# Blink_Blink_Beep_Boop.net
KiCad netlist of a schematic drawn in Altium Designer
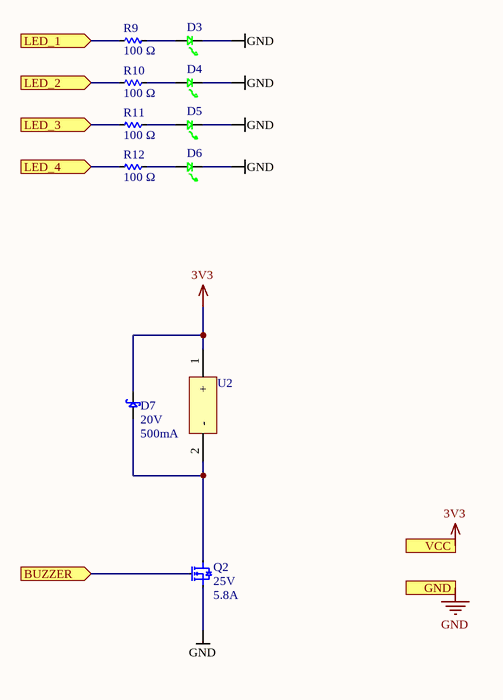
[diagram p0: Blink_Blink_Beep_Boop.SchDoc]

(export (version "E")
  (design (tool "Eeschema 10.0.6"))
  (components
    (comp (ref "D3")
      (value "LED_LY971")
      (footprint "0805_Diode")
      (description "LED 0805 GREEN 20MA")
      (fields
        (field (name "MANUFACTURER") "OSRAM Opto Semiconductors Inc")
        (field (name "MANUFACTURER PART NUMBER") "LG R971-KN-1")
      )
      (libsource (lib "Stanford Student Space Initiative") (part "LED_LY971"))
    )
    (comp (ref "D4")
      (value "LED_LY971")
      (footprint "0805_Diode")
      (description "LED 0805 GREEN 20MA")
      (fields
        (field (name "MANUFACTURER") "OSRAM Opto Semiconductors Inc")
        (field (name "MANUFACTURER PART NUMBER") "LG R971-KN-1")
      )
      (libsource (lib "Stanford Student Space Initiative") (part "LED_LY971"))
    )
    (comp (ref "D5")
      (value "LED_LY971")
      (footprint "0805_Diode")
      (description "LED 0805 GREEN 20MA")
      (fields
        (field (name "MANUFACTURER") "OSRAM Opto Semiconductors Inc")
        (field (name "MANUFACTURER PART NUMBER") "LG R971-KN-1")
      )
      (libsource (lib "Stanford Student Space Initiative") (part "LED_LY971"))
    )
    (comp (ref "D6")
      (value "LED_LY971")
      (footprint "0805_Diode")
      (description "LED 0805 GREEN 20MA")
      (fields
        (field (name "MANUFACTURER") "OSRAM Opto Semiconductors Inc")
        (field (name "MANUFACTURER PART NUMBER") "LG R971-KN-1")
      )
      (libsource (lib "Stanford Student Space Initiative") (part "LED_LY971"))
    )
    (comp (ref "D7")
      (value "Symbol")
      (footprint "SOD123")
      (description "DIODE SCHOTTKY 0.5A 20V SOD-123")
      (fields
        (field (name "MANUFACTURER") "Fairchild Semiconductor")
        (field (name "MANUFACTURER PART NUMBER") "MBR0520L")
        (field (name "VOLTAGE - DC REVERSE (VR) (MAX)") "20V")
        (field (name "CURRENT - AVERAGE RECTIFIED (IO)") "500mA")
      )
      (libsource (lib "Stanford Student Space Initiative") (part "Symbol"))
    )
    (comp (ref "Q2")
      (value "Symbol")
      (footprint "3SOT23")
      (description "MOSFET N-CH 25V 5.8A SOT23")
      (fields
        (field (name "MANUFACTURER") "International Rectifier")
        (field (name "MANUFACTURER PART NUMBER") "IRFML8244TRPBF")
        (field (name "DRAIN TO SOURCE VOLTAGE (VDSS)") "25V")
        (field (name "CURRENT - CONTINUOUS DRAIN (ID) @ 25° C") "5.8A")
      )
      (libsource (lib "") (part "Symbol_1"))
    )
    (comp (ref "R9")
      (value "311-100HRCT-ND")
      (footprint "R0603")
      (description "RES SMD 100 OHM 1% 1/10W 0603")
      (fields
        (field (name "MANUFACTURER PART NUMBER") "RC0603FR-07100RL")
        (field (name "MANUFACTURER") "Yageo")
        (field (name "RESISTANCE") "100 Ω")
      )
      (libsource (lib "Stanford Student Space Initiative") (part "__template_resistor"))
    )
    (comp (ref "R10")
      (value "311-100HRCT-ND")
      (footprint "R0603")
      (description "RES SMD 100 OHM 1% 1/10W 0603")
      (fields
        (field (name "MANUFACTURER PART NUMBER") "RC0603FR-07100RL")
        (field (name "MANUFACTURER") "Yageo")
        (field (name "RESISTANCE") "100 Ω")
      )
      (libsource (lib "Stanford Student Space Initiative") (part "__template_resistor"))
    )
    (comp (ref "R11")
      (value "311-100HRCT-ND")
      (footprint "R0603")
      (description "RES SMD 100 OHM 1% 1/10W 0603")
      (fields
        (field (name "MANUFACTURER PART NUMBER") "RC0603FR-07100RL")
        (field (name "MANUFACTURER") "Yageo")
        (field (name "RESISTANCE") "100 Ω")
      )
      (libsource (lib "Stanford Student Space Initiative") (part "__template_resistor"))
    )
    (comp (ref "R12")
      (value "311-100HRCT-ND")
      (footprint "R0603")
      (description "RES SMD 100 OHM 1% 1/10W 0603")
      (fields
        (field (name "MANUFACTURER PART NUMBER") "RC0603FR-07100RL")
        (field (name "MANUFACTURER") "Yageo")
        (field (name "RESISTANCE") "100 Ω")
      )
      (libsource (lib "Stanford Student Space Initiative") (part "__template_resistor"))
    )
    (comp (ref "U2")
      (value "BUZ_SMT-0540-T-7-R")
      (footprint "BUZ_SMT-0540-T-7-R")
      (description "Peak-Peak Signal Buzzer Single Tone 4kHz Magnetic 2 ~ 4V 78dB @ 3V, 10cm")
      (fields
        (field (name "MANUFACTURER") "PUI Audio, Inc.")
        (field (name "MANUFACTURER PART NUMBER") "SMT-0540-T-7-R")
      )
      (libsource (lib "Stanford Student Space Initiative") (part "BUZ_SMT-0540-T-7-R"))
    )
  )
  (nets
    (net (code "1") (name "/BUZZER") (class "Default") (node (ref "Q2") (pin "1") (pintype "passive")))
    (net (code "2") (name "/LED_1") (class "Default")
      (node (ref "R9") (pin "1") (pinfunction "1_1") (pintype "passive"))
    )
    (net (code "3") (name "/LED_2") (class "Default")
      (node (ref "R10") (pin "1") (pinfunction "1_1") (pintype "passive"))
    )
    (net (code "4") (name "/LED_3") (class "Default")
      (node (ref "R11") (pin "1") (pinfunction "1_1") (pintype "passive"))
    )
    (net (code "5") (name "/LED_4") (class "Default")
      (node (ref "R12") (pin "1") (pinfunction "1_1") (pintype "passive"))
    )
    (net (code "6") (name "3V3") (class "Default")
      (node (ref "D7") (pin "2") (pintype "passive"))
      (node (ref "U2") (pin "1") (pinfunction "+_1") (pintype "passive"))
    )
    (net (code "7") (name "GND") (class "Default")
      (node (ref "D3") (pin "1") (pintype "passive"))
      (node (ref "D4") (pin "1") (pintype "passive"))
      (node (ref "D5") (pin "1") (pintype "passive"))
      (node (ref "D6") (pin "1") (pintype "passive"))
      (node (ref "Q2") (pin "2") (pintype "passive"))
    )
    (net (code "8") (name "Net-(D3-Pad2)") (class "Default")
      (node (ref "D3") (pin "2") (pintype "passive"))
      (node (ref "R9") (pin "2") (pinfunction "2_2") (pintype "passive"))
    )
    (net (code "9") (name "Net-(D4-Pad2)") (class "Default")
      (node (ref "D4") (pin "2") (pintype "passive"))
      (node (ref "R10") (pin "2") (pinfunction "2_2") (pintype "passive"))
    )
    (net (code "10") (name "Net-(D5-Pad2)") (class "Default")
      (node (ref "D5") (pin "2") (pintype "passive"))
      (node (ref "R11") (pin "2") (pinfunction "2_2") (pintype "passive"))
    )
    (net (code "11") (name "Net-(D6-Pad2)") (class "Default")
      (node (ref "D6") (pin "2") (pintype "passive"))
      (node (ref "R12") (pin "2") (pinfunction "2_2") (pintype "passive"))
    )
    (net (code "12") (name "Net-(U2--)") (class "Default")
      (node (ref "D7") (pin "1") (pintype "passive"))
      (node (ref "Q2") (pin "3") (pintype "passive"))
      (node (ref "U2") (pin "2") (pinfunction "-_2") (pintype "passive"))
    )
  )
)
